# treiber.net
KiCad netlist of a schematic drawn in EAGLE
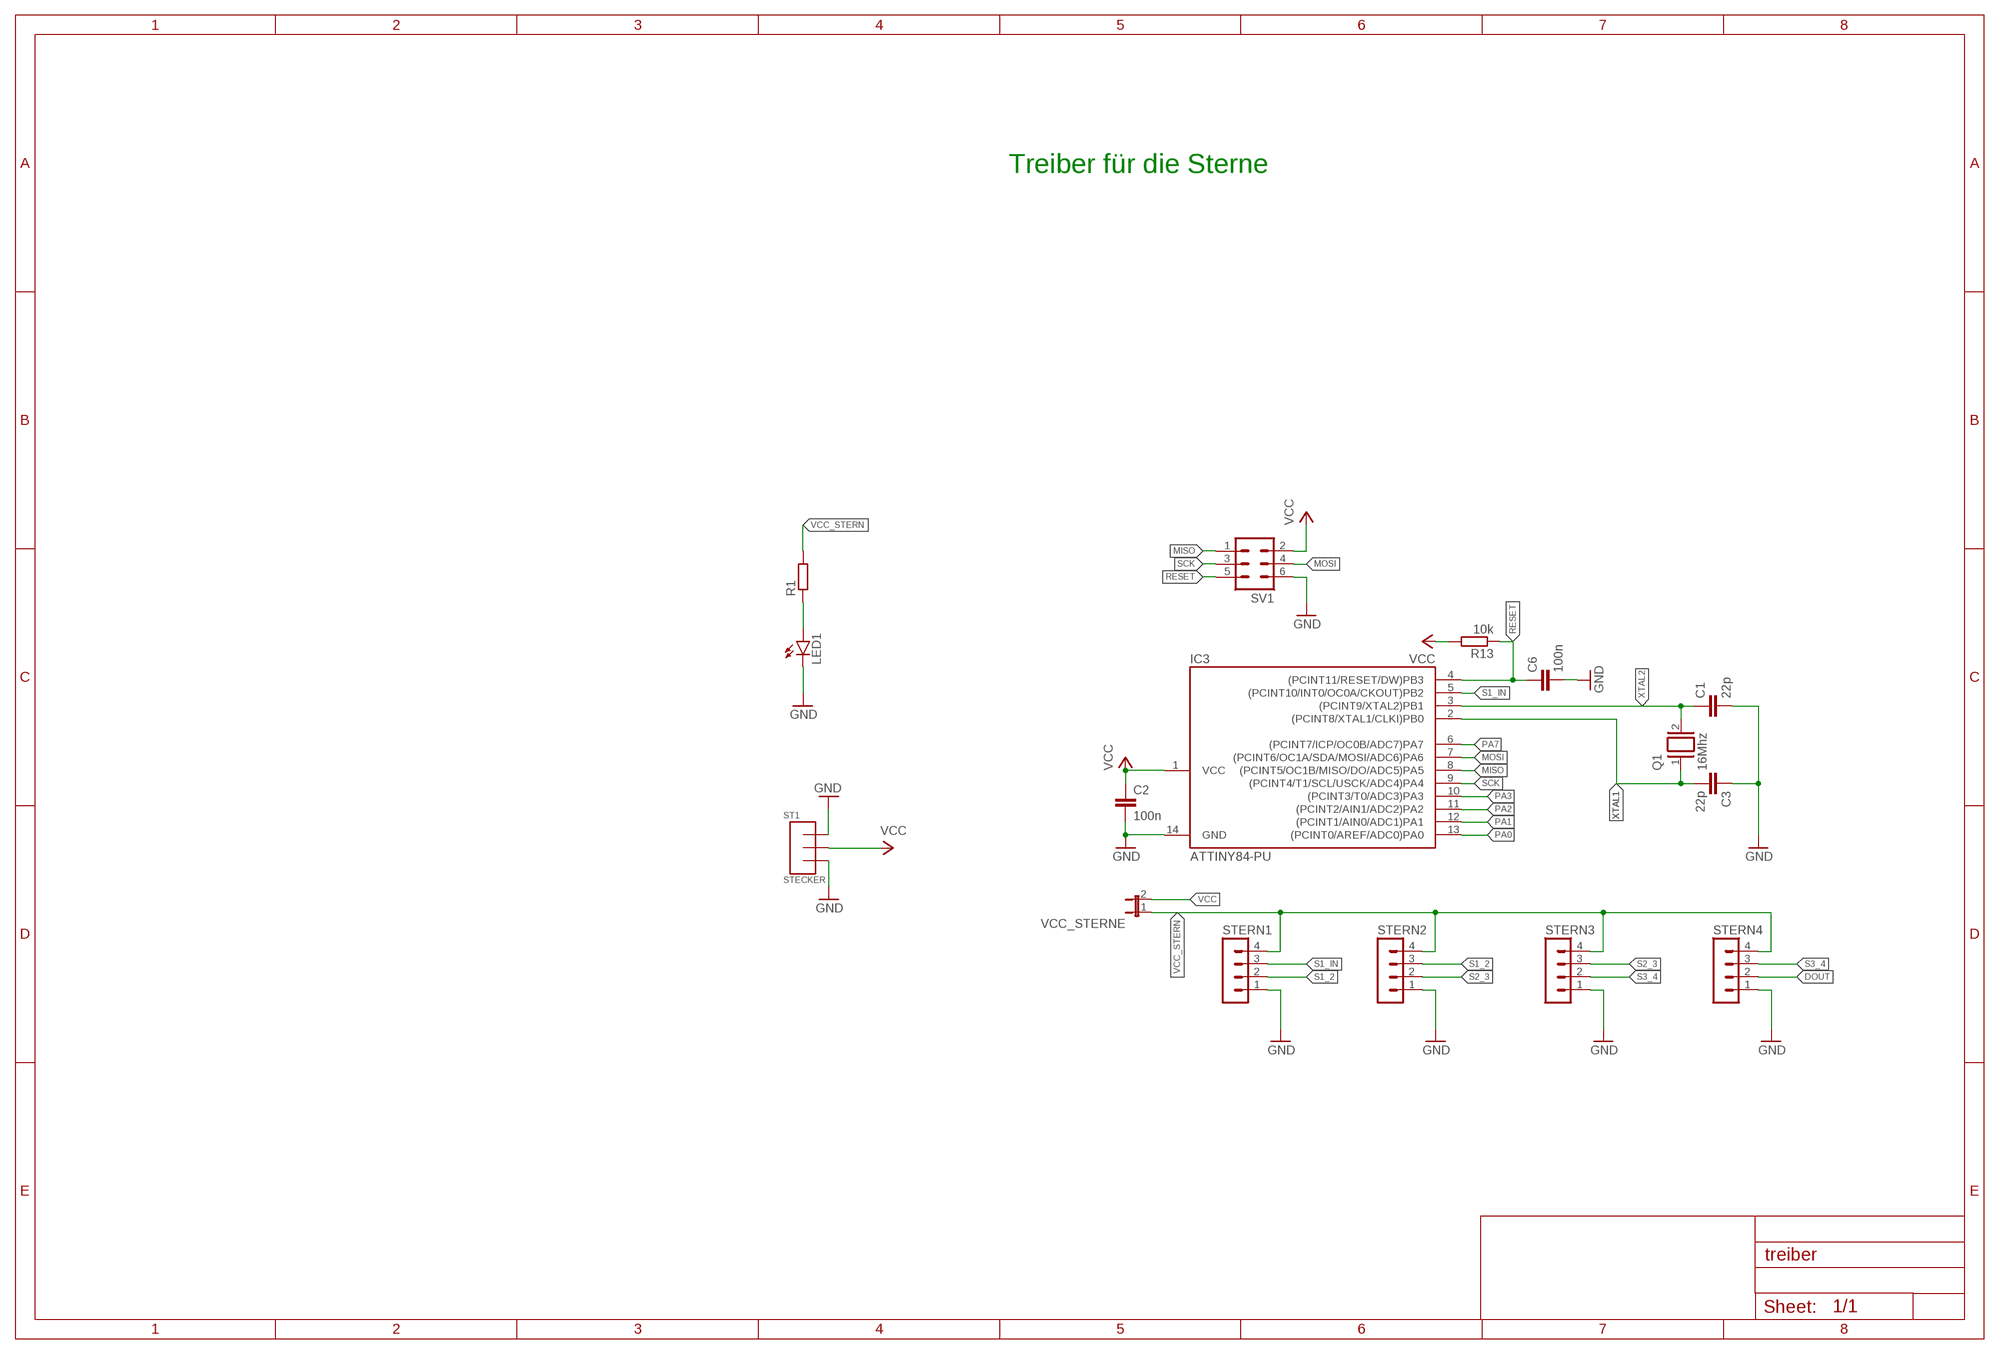
[diagram p0: schematic, sheet 1]

(export (version "E")
  (design (tool "Eeschema 10.0.6"))
  (components
    (comp (ref "C1")
      (value "22p")
      (footprint "eagle-import:C025-024X044")
      (libsource (lib "eagle-import") (part "C-EU025-024X044"))
    )
    (comp (ref "C2")
      (value "100n")
      (footprint "eagle-import:C0805")
      (libsource (lib "eagle-import") (part "C-EUC0805"))
    )
    (comp (ref "C3")
      (value "22p")
      (footprint "eagle-import:C025-024X044")
      (libsource (lib "eagle-import") (part "C-EU025-024X044"))
    )
    (comp (ref "C6")
      (value "100n")
      (footprint "eagle-import:C0805")
      (libsource (lib "eagle-import") (part "C-EUC0805"))
    )
    (comp (ref "IC3")
      (value "ATTINY84-PU")
      (footprint "eagle-import:DIL14")
      (libsource (lib "eagle-import") (part "ATTINY24/44/84-PU"))
    )
    (comp (ref "LED1")
      (value "LEDSML0805")
      (footprint "eagle-import:SML0805")
      (libsource (lib "eagle-import") (part "LEDSML0805"))
    )
    (comp (ref "Q1")
      (value "16Mhz")
      (footprint "eagle-import:QS")
      (libsource (lib "eagle-import") (part "XTAL/S"))
    )
    (comp (ref "R1")
      (value "R-EU_R0805")
      (footprint "eagle-import:R0805")
      (libsource (lib "eagle-import") (part "R-EU_R0805"))
    )
    (comp (ref "R13")
      (value "10k")
      (footprint "eagle-import:R0805")
      (libsource (lib "eagle-import") (part "R-EU_R0805"))
    )
    (comp (ref "ST1")
      (value "STECKER")
      (footprint "eagle-import:STROMSTECKER")
      (libsource (lib "eagle-import") (part "STECKER"))
    )
    (comp (ref "STERN1")
      (value "MA04-1")
      (footprint "eagle-import:MA04-1")
      (libsource (lib "eagle-import") (part "MA04-1"))
    )
    (comp (ref "STERN2")
      (value "MA04-1")
      (footprint "eagle-import:MA04-1")
      (libsource (lib "eagle-import") (part "MA04-1"))
    )
    (comp (ref "STERN3")
      (value "MA04-1")
      (footprint "eagle-import:MA04-1")
      (libsource (lib "eagle-import") (part "MA04-1"))
    )
    (comp (ref "STERN4")
      (value "MA04-1")
      (footprint "eagle-import:MA04-1")
      (libsource (lib "eagle-import") (part "MA04-1"))
    )
    (comp (ref "SV1")
      (value "MA03-2")
      (footprint "eagle-import:MA03-2")
      (libsource (lib "eagle-import") (part "MA03-2"))
    )
    (comp (ref "VCC_STERNE")
      (value "JP1E")
      (footprint "eagle-import:JP1")
      (libsource (lib "eagle-import") (part "JP1E"))
    )
  )
  (nets
    (net (code "1") (name "DOUT") (class "Default")
      (node (ref "STERN4") (pin "2") (pinfunction "2_2") (pintype "passive"))
    )
    (net (code "2") (name "GND") (class "Default")
      (node (ref "C1") (pin "2") (pinfunction "2_2") (pintype "passive"))
      (node (ref "C2") (pin "2") (pinfunction "2_2") (pintype "passive"))
      (node (ref "C3") (pin "1") (pinfunction "1_1") (pintype "passive"))
      (node (ref "C6") (pin "2") (pinfunction "2_2") (pintype "passive"))
      (node (ref "IC3") (pin "14") (pinfunction "GND_14") (pintype "power_in"))
      (node (ref "LED1") (pin "C") (pinfunction "C_C") (pintype "passive"))
      (node (ref "ST1") (pin "LINKS") (pinfunction "LINKS_LINKS") (pintype "bidirectional"))
      (node (ref "ST1") (pin "RECHTS") (pinfunction "RECHTS_RECHTS") (pintype "bidirectional"))
      (node (ref "STERN1") (pin "1") (pinfunction "1_1") (pintype "passive"))
      (node (ref "STERN2") (pin "1") (pinfunction "1_1") (pintype "passive"))
      (node (ref "STERN3") (pin "1") (pinfunction "1_1") (pintype "passive"))
      (node (ref "STERN4") (pin "1") (pinfunction "1_1") (pintype "passive"))
      (node (ref "SV1") (pin "6") (pinfunction "6_6") (pintype "passive"))
    )
    (net (code "3") (name "MISO") (class "Default")
      (node (ref "IC3") (pin "8") (pinfunction "(PCINT5/OC1B/MISO/DO/ADC5)PA5_8") (pintype "bidirectional"))
      (node (ref "SV1") (pin "1") (pinfunction "1_1") (pintype "passive"))
    )
    (net (code "4") (name "MOSI") (class "Default")
      (node (ref "IC3") (pin "7") (pinfunction "(PCINT6/OC1A/SDA/MOSI/ADC6)PA6_7") (pintype "bidirectional"))
      (node (ref "SV1") (pin "4") (pinfunction "4_4") (pintype "passive"))
    )
    (net (code "5") (name "Net-(LED1-PadA)") (class "Default")
      (node (ref "LED1") (pin "A") (pinfunction "A_A") (pintype "passive"))
      (node (ref "R1") (pin "1") (pinfunction "1_1") (pintype "passive"))
    )
    (net (code "6") (name "PA0") (class "Default")
      (node (ref "IC3") (pin "13") (pinfunction "(PCINT0/AREF/ADC0)PA0_13") (pintype "bidirectional"))
    )
    (net (code "7") (name "PA1") (class "Default")
      (node (ref "IC3") (pin "12") (pinfunction "(PCINT1/AIN0/ADC1)PA1_12") (pintype "bidirectional"))
    )
    (net (code "8") (name "PA2") (class "Default")
      (node (ref "IC3") (pin "11") (pinfunction "(PCINT2/AIN1/ADC2)PA2_11") (pintype "bidirectional"))
    )
    (net (code "9") (name "PA3") (class "Default")
      (node (ref "IC3") (pin "10") (pinfunction "(PCINT3/T0/ADC3)PA3_10") (pintype "bidirectional"))
    )
    (net (code "10") (name "PA7") (class "Default")
      (node (ref "IC3") (pin "6") (pinfunction "(PCINT7/ICP/OC0B/ADC7)PA7_6") (pintype "bidirectional"))
    )
    (net (code "11") (name "RESET") (class "Default")
      (node (ref "C6") (pin "1") (pinfunction "1_1") (pintype "passive"))
      (node (ref "IC3") (pin "4") (pinfunction "(PCINT11/RESET/DW)PB3_4") (pintype "bidirectional"))
      (node (ref "R13") (pin "1") (pinfunction "1_1") (pintype "passive"))
      (node (ref "SV1") (pin "5") (pinfunction "5_5") (pintype "passive"))
    )
    (net (code "12") (name "S1_2") (class "Default")
      (node (ref "STERN1") (pin "2") (pinfunction "2_2") (pintype "passive"))
      (node (ref "STERN2") (pin "3") (pinfunction "3_3") (pintype "passive"))
    )
    (net (code "13") (name "S1_IN") (class "Default")
      (node (ref "IC3") (pin "5") (pinfunction "(PCINT10/INT0/OC0A/CKOUT)PB2_5") (pintype "bidirectional"))
      (node (ref "STERN1") (pin "3") (pinfunction "3_3") (pintype "passive"))
    )
    (net (code "14") (name "S2_3") (class "Default")
      (node (ref "STERN2") (pin "2") (pinfunction "2_2") (pintype "passive"))
      (node (ref "STERN3") (pin "3") (pinfunction "3_3") (pintype "passive"))
    )
    (net (code "15") (name "S3_4") (class "Default")
      (node (ref "STERN3") (pin "2") (pinfunction "2_2") (pintype "passive"))
      (node (ref "STERN4") (pin "3") (pinfunction "3_3") (pintype "passive"))
    )
    (net (code "16") (name "SCK") (class "Default")
      (node (ref "IC3") (pin "9") (pinfunction "(PCINT4/T1/SCL/USCK/ADC4)PA4_9") (pintype "bidirectional"))
      (node (ref "SV1") (pin "3") (pinfunction "3_3") (pintype "passive"))
    )
    (net (code "17") (name "VCC") (class "Default")
      (node (ref "C2") (pin "1") (pinfunction "1_1") (pintype "passive"))
      (node (ref "IC3") (pin "1") (pinfunction "VCC_1") (pintype "power_in"))
      (node (ref "R13") (pin "2") (pinfunction "2_2") (pintype "passive"))
      (node (ref "ST1") (pin "INNEN") (pinfunction "INNEN_INNEN") (pintype "bidirectional"))
      (node (ref "SV1") (pin "2") (pinfunction "2_2") (pintype "passive"))
      (node (ref "VCC_STERNE") (pin "2") (pinfunction "2_2") (pintype "passive"))
    )
    (net (code "18") (name "VCC_STERN") (class "Default")
      (node (ref "R1") (pin "2") (pinfunction "2_2") (pintype "passive"))
      (node (ref "STERN1") (pin "4") (pinfunction "4_4") (pintype "passive"))
      (node (ref "STERN2") (pin "4") (pinfunction "4_4") (pintype "passive"))
      (node (ref "STERN3") (pin "4") (pinfunction "4_4") (pintype "passive"))
      (node (ref "STERN4") (pin "4") (pinfunction "4_4") (pintype "passive"))
      (node (ref "VCC_STERNE") (pin "1") (pinfunction "1_1") (pintype "passive"))
    )
    (net (code "19") (name "XTAL1") (class "Default")
      (node (ref "C3") (pin "2") (pinfunction "2_2") (pintype "passive"))
      (node (ref "IC3") (pin "2") (pinfunction "(PCINT8/XTAL1/CLKI)PB0_2") (pintype "bidirectional"))
      (node (ref "Q1") (pin "1") (pinfunction "1_1") (pintype "passive"))
    )
    (net (code "20") (name "XTAL2") (class "Default")
      (node (ref "C1") (pin "1") (pinfunction "1_1") (pintype "passive"))
      (node (ref "IC3") (pin "3") (pinfunction "(PCINT9/XTAL2)PB1_3") (pintype "bidirectional"))
      (node (ref "Q1") (pin "2") (pinfunction "2_2") (pintype "passive"))
    )
  )
)
